# MicroMultimeter_PWR_Sch.net
KiCad netlist of a schematic drawn in Altium Designer
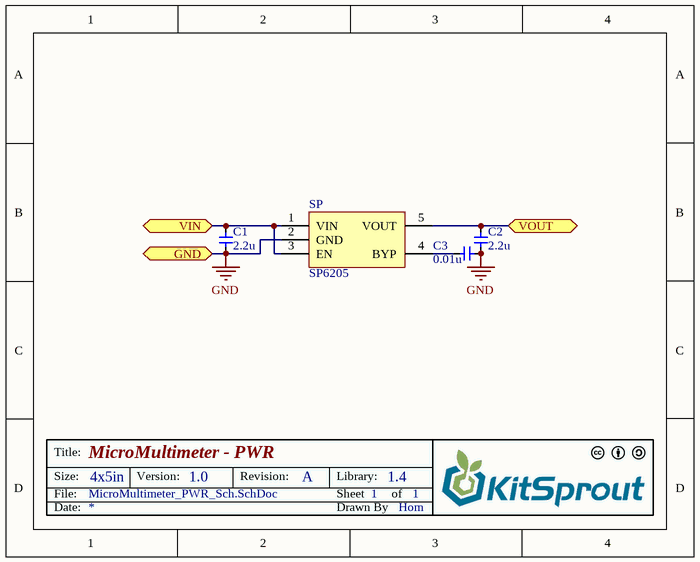
[diagram p0: MicroMultimeter_PWR_Sch.SchDoc]

(export (version "E")
  (design (tool "Eeschema 10.0.6"))
  (components
    (comp (ref "C1")
      (value "2.2u")
      (footprint "PCB_PassiveCap:CAP_0603")
      (description "Capacitor")
      (fields (field (name "Comment") "Cap_0603"))
      (libsource (lib "SCH_Passive") (part "Cap_0603"))
    )
    (comp (ref "C2")
      (value "2.2u")
      (footprint "PCB_PassiveCap:CAP_0603")
      (description "Capacitor")
      (fields (field (name "Comment") "Cap_0603"))
      (libsource (lib "SCH_Passive") (part "Cap_0603"))
    )
    (comp (ref "C3")
      (value "0.01u")
      (footprint "PCB_PassiveCap:CAP_0603")
      (description "Capacitor")
      (fields (field (name "Comment") "Cap_0603"))
      (libsource (lib "SCH_Passive") (part "Cap_0603"))
    )
    (comp (ref "SP")
      (value "SP6205")
      (footprint "PCB_IntegratedCircuit:SOT23-5")
      (description "Power")
      (libsource (lib "SCH_IntegratedCircuit") (part "SP6205"))
    )
  )
  (nets
    (net (code "1") (name "/VIN") (class "Default")
      (node (ref "C1") (pin "2") (pinfunction "2_2") (pintype "passive"))
      (node (ref "SP") (pin "1") (pinfunction "VIN_1") (pintype "passive"))
      (node (ref "SP") (pin "3") (pinfunction "EN_3") (pintype "power_in"))
    )
    (net (code "2") (name "/VOUT") (class "Default")
      (node (ref "C2") (pin "2") (pinfunction "2_2") (pintype "passive"))
      (node (ref "SP") (pin "5") (pinfunction "VOUT_5") (pintype "passive"))
    )
    (net (code "3") (name "GND") (class "Default")
      (node (ref "C1") (pin "1") (pinfunction "1_1") (pintype "passive"))
      (node (ref "C2") (pin "1") (pinfunction "1_1") (pintype "passive"))
      (node (ref "C3") (pin "1") (pinfunction "1_1") (pintype "passive"))
      (node (ref "SP") (pin "2") (pinfunction "GND_2") (pintype "passive"))
    )
    (net (code "4") (name "Net-(SP-BYP)") (class "Default")
      (node (ref "C3") (pin "2") (pinfunction "2_2") (pintype "passive"))
      (node (ref "SP") (pin "4") (pinfunction "BYP_4") (pintype "passive"))
    )
  )
)
